# LDO.net
KiCad netlist of a schematic drawn in Altium Designer
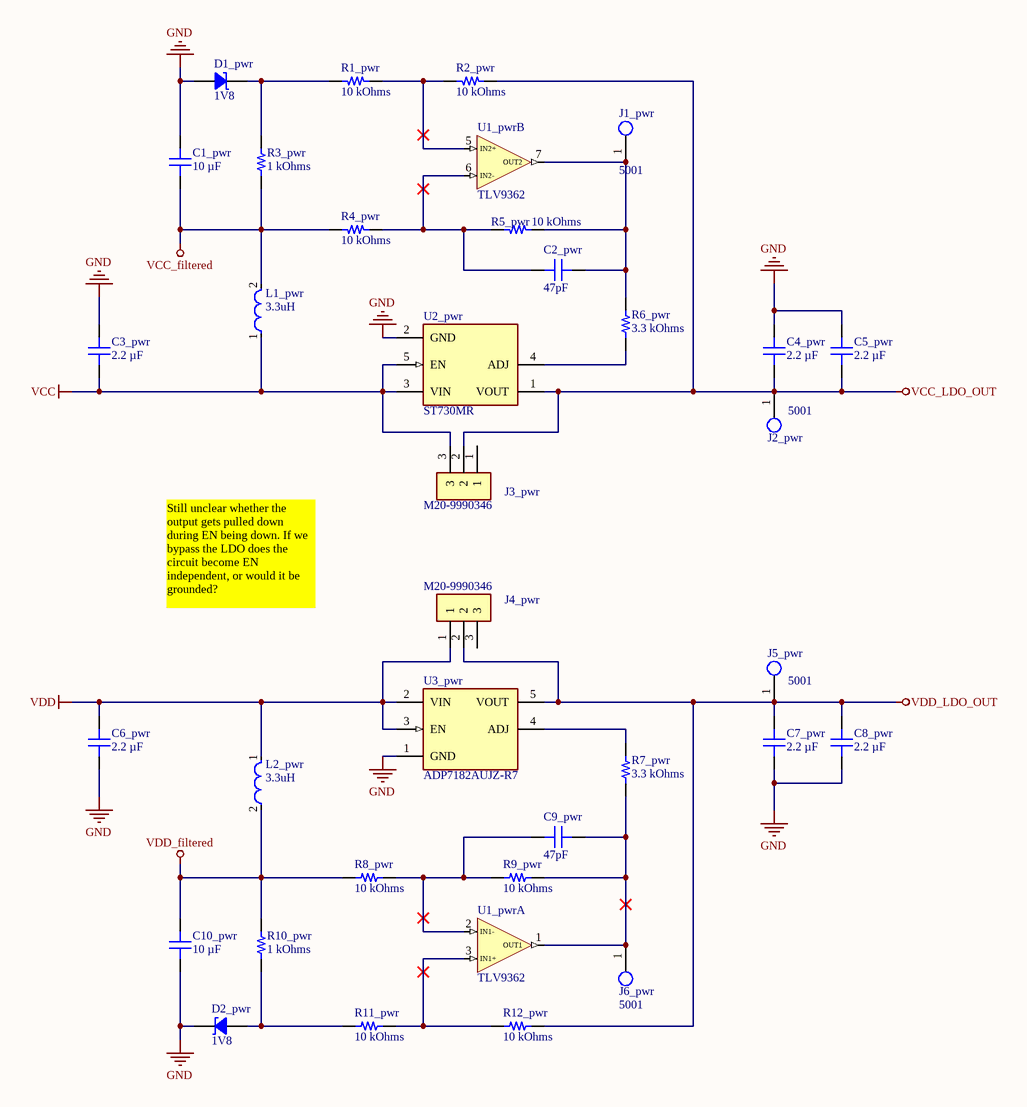
[diagram p0: LDO.SchDoc]

(export (version "E")
  (design (tool "Eeschema 10.0.6"))
  (components
    (comp (ref "C1_pwr")
      (value "10 µF")
      (footprint "CAP 1206_3216 - 0.8MM")
      (description "CAP CER 10UF 25V X7R 1206")
      (fields
        (field (name "PART NUMBER") "885012208069")
        (field (name "CAPACITANCE") "10 µF")
        (field (name "MANUFACTURER") "Würth Elektronik")
      )
      (libsource (lib "Celestial Altium Library - altium_library") (part "Capacitor"))
    )
    (comp (ref "C2_pwr")
      (value "47pF")
      (footprint "CAP 1206_3216 - 1.8MM")
      (description "CAP CER 47PF 1KV C0G/NP0 1206")
      (fields
        (field (name "PART NUMBER") "1206AA470KAT1A")
        (field (name "CAPACITANCE") "47pF")
        (field (name "MANUFACTURER") "AVX Corporation")
      )
      (libsource (lib "Celestial Altium Library - altium_library") (part "Capacitor"))
    )
    (comp (ref "C3_pwr")
      (value "2.2 µF")
      (footprint "CAP 1206_3216 - 0.8MM")
      (description "CAP CER 2.2UF 25V X7R 1206")
      (fields
        (field (name "PART NUMBER") "885382208001")
        (field (name "CAPACITANCE") "2.2 µF")
        (field (name "MANUFACTURER") "Würth Elektronik")
      )
      (libsource (lib "Celestial Altium Library - altium_library") (part "Capacitor"))
    )
    (comp (ref "C4_pwr")
      (value "2.2 µF")
      (footprint "CAP 1206_3216 - 0.8MM")
      (description "CAP CER 2.2UF 25V X7R 1206")
      (fields
        (field (name "PART NUMBER") "885382208001")
        (field (name "CAPACITANCE") "2.2 µF")
        (field (name "MANUFACTURER") "Würth Elektronik")
      )
      (libsource (lib "Celestial Altium Library - altium_library") (part "Capacitor"))
    )
    (comp (ref "C5_pwr")
      (value "2.2 µF")
      (footprint "CAP 1206_3216 - 0.8MM")
      (description "CAP CER 2.2UF 25V X7R 1206")
      (fields
        (field (name "PART NUMBER") "885382208001")
        (field (name "CAPACITANCE") "2.2 µF")
        (field (name "MANUFACTURER") "Würth Elektronik")
      )
      (libsource (lib "Celestial Altium Library - altium_library") (part "Capacitor"))
    )
    (comp (ref "C6_pwr")
      (value "2.2 µF")
      (footprint "CAP 1206_3216 - 0.8MM")
      (description "CAP CER 2.2UF 25V X7R 1206")
      (fields
        (field (name "PART NUMBER") "885382208001")
        (field (name "CAPACITANCE") "2.2 µF")
        (field (name "MANUFACTURER") "Würth Elektronik")
      )
      (libsource (lib "Celestial Altium Library - altium_library") (part "Capacitor"))
    )
    (comp (ref "C7_pwr")
      (value "2.2 µF")
      (footprint "CAP 1206_3216 - 0.8MM")
      (description "CAP CER 2.2UF 25V X7R 1206")
      (fields
        (field (name "PART NUMBER") "885382208001")
        (field (name "CAPACITANCE") "2.2 µF")
        (field (name "MANUFACTURER") "Würth Elektronik")
      )
      (libsource (lib "Celestial Altium Library - altium_library") (part "Capacitor"))
    )
    (comp (ref "C8_pwr")
      (value "2.2 µF")
      (footprint "CAP 1206_3216 - 0.8MM")
      (description "CAP CER 2.2UF 25V X7R 1206")
      (fields
        (field (name "PART NUMBER") "885382208001")
        (field (name "CAPACITANCE") "2.2 µF")
        (field (name "MANUFACTURER") "Würth Elektronik")
      )
      (libsource (lib "Celestial Altium Library - altium_library") (part "Capacitor"))
    )
    (comp (ref "C9_pwr")
      (value "47pF")
      (footprint "CAP 1206_3216 - 1.8MM")
      (description "CAP CER 47PF 1KV C0G/NP0 1206")
      (fields
        (field (name "PART NUMBER") "1206AA470KAT1A")
        (field (name "CAPACITANCE") "47pF")
        (field (name "MANUFACTURER") "AVX Corporation")
      )
      (libsource (lib "Celestial Altium Library - altium_library") (part "Capacitor"))
    )
    (comp (ref "C10_pwr")
      (value "10 µF")
      (footprint "CAP 1206_3216 - 0.8MM")
      (description "CAP CER 10UF 25V X7R 1206")
      (fields
        (field (name "PART NUMBER") "885012208069")
        (field (name "CAPACITANCE") "10 µF")
        (field (name "MANUFACTURER") "Würth Elektronik")
      )
      (libsource (lib "Celestial Altium Library - altium_library") (part "Capacitor"))
    )
    (comp (ref "D1_pwr")
      (value "1V8")
      (footprint "SOD323")
      (libsource (lib "za_koncar") (part "BZX38450-C1V8X"))
    )
    (comp (ref "D2_pwr")
      (value "1V8")
      (footprint "SOD323")
      (libsource (lib "za_koncar") (part "BZX38450-C1V8X"))
    )
    (comp (ref "J1_pwr")
      (value "5001")
      (footprint "FP-5001-MFG")
      (description "PC TEST POINT MINIATURE BLACK")
      (libsource (lib "za_koncar") (part "CMP-2000-05181-2"))
    )
    (comp (ref "J2_pwr")
      (value "5001")
      (footprint "FP-5001-MFG")
      (description "PC TEST POINT MINIATURE BLACK")
      (libsource (lib "za_koncar") (part "CMP-2000-05181-2"))
    )
    (comp (ref "J3_pwr")
      (value "M20-9990346")
      (footprint "HDRV3W64P0X254_1X3_762X254X864P - duplicate")
      (description "Connector")
      (fields (field (name "MOUSER PART NUMBER") "855-M20-9990346"))
      (libsource (lib "") (part "M20-9990346_1"))
    )
    (comp (ref "J4_pwr")
      (value "M20-9990346")
      (footprint "HDRV3W64P0X254_1X3_762X254X864P - duplicate")
      (description "Connector")
      (fields (field (name "MOUSER PART NUMBER") "855-M20-9990346"))
      (libsource (lib "za_koncar") (part "M20-9990346"))
    )
    (comp (ref "J5_pwr")
      (value "5001")
      (footprint "FP-5001-MFG")
      (description "PC TEST POINT MINIATURE BLACK")
      (libsource (lib "za_koncar") (part "CMP-2000-05181-2"))
    )
    (comp (ref "J6_pwr")
      (value "5001")
      (footprint "FP-5001-MFG")
      (description "PC TEST POINT MINIATURE BLACK")
      (libsource (lib "za_koncar") (part "CMP-2000-05181-2"))
    )
    (comp (ref "L1_pwr")
      (value "3.3uH")
      (footprint "FP-MLZ2012-1_25-IPC_B")
      (description "Shielded Multilayer Inductor 3.3uH ±20% 500mA 260mΩ SMD 0805")
      (fields (field (name "TOLERANCE") "20%"))
      (libsource (lib "") (part "MLZ2012M_1"))
    )
    (comp (ref "L2_pwr")
      (value "3.3uH")
      (footprint "FP-MLZ2012-1_25-IPC_B")
      (description "Shielded Multilayer Inductor 3.3uH ±20% 500mA 260mΩ SMD 0805")
      (fields (field (name "TOLERANCE") "20%"))
      (libsource (lib "za_koncar") (part "MLZ2012M"))
    )
    (comp (ref "R1_pwr")
      (value "10 kOhms")
      (footprint "YAGEO RES 1206_3216")
      (description "RES SMD 10K OHM 1% 1/4W 1206")
      (fields (field (name "PART NUMBER") "RT1206FRE0710KL") (field (name "MANUFACTURER") "Yageo"))
      (libsource (lib "Celestial Altium Library - altium_library") (part "Resistor"))
    )
    (comp (ref "R2_pwr")
      (value "10 kOhms")
      (footprint "YAGEO RES 1206_3216")
      (description "RES SMD 10K OHM 1% 1/4W 1206")
      (fields (field (name "PART NUMBER") "RT1206FRE0710KL") (field (name "MANUFACTURER") "Yageo"))
      (libsource (lib "Celestial Altium Library - altium_library") (part "Resistor"))
    )
    (comp (ref "R3_pwr")
      (value "1 kOhms")
      (footprint "YAGEO RES 1206_3216")
      (description "RES SMD 1K OHM 1% 1/4W 1206")
      (fields (field (name "PART NUMBER") "RT1206FRE071KL") (field (name "MANUFACTURER") "Yageo"))
      (libsource (lib "Celestial Altium Library - altium_library") (part "Resistor"))
    )
    (comp (ref "R4_pwr")
      (value "10 kOhms")
      (footprint "YAGEO RES 1206_3216")
      (description "RES SMD 10K OHM 1% 1/4W 1206")
      (fields (field (name "PART NUMBER") "RT1206FRE0710KL") (field (name "MANUFACTURER") "Yageo"))
      (libsource (lib "Celestial Altium Library - altium_library") (part "Resistor"))
    )
    (comp (ref "R5_pwr")
      (value "10 kOhms")
      (footprint "YAGEO RES 1206_3216")
      (description "RES SMD 10K OHM 1% 1/4W 1206")
      (fields (field (name "PART NUMBER") "RT1206FRE0710KL") (field (name "MANUFACTURER") "Yageo"))
      (libsource (lib "Celestial Altium Library - altium_library") (part "Resistor"))
    )
    (comp (ref "R6_pwr")
      (value "3.3 kOhms")
      (footprint "YAGEO RES 1206_3216")
      (description "RES SMD 3.3K OHM 1% 1/4W 1206")
      (fields (field (name "PART NUMBER") "RT1206FRE073K3L") (field (name "MANUFACTURER") "Yageo"))
      (libsource (lib "Celestial Altium Library - altium_library") (part "Resistor"))
    )
    (comp (ref "R7_pwr")
      (value "3.3 kOhms")
      (footprint "YAGEO RES 1206_3216")
      (description "RES SMD 3.3K OHM 1% 1/4W 1206")
      (fields (field (name "PART NUMBER") "RT1206FRE073K3L") (field (name "MANUFACTURER") "Yageo"))
      (libsource (lib "Celestial Altium Library - altium_library") (part "Resistor"))
    )
    (comp (ref "R8_pwr")
      (value "10 kOhms")
      (footprint "YAGEO RES 1206_3216")
      (description "RES SMD 10K OHM 1% 1/4W 1206")
      (fields (field (name "PART NUMBER") "RT1206FRE0710KL") (field (name "MANUFACTURER") "Yageo"))
      (libsource (lib "Celestial Altium Library - altium_library") (part "Resistor"))
    )
    (comp (ref "R9_pwr")
      (value "10 kOhms")
      (footprint "YAGEO RES 1206_3216")
      (description "RES SMD 10K OHM 1% 1/4W 1206")
      (fields (field (name "PART NUMBER") "RT1206FRE0710KL") (field (name "MANUFACTURER") "Yageo"))
      (libsource (lib "Celestial Altium Library - altium_library") (part "Resistor"))
    )
    (comp (ref "R10_pwr")
      (value "1 kOhms")
      (footprint "YAGEO RES 1206_3216")
      (description "RES SMD 1K OHM 1% 1/4W 1206")
      (fields (field (name "PART NUMBER") "RT1206FRE071KL") (field (name "MANUFACTURER") "Yageo"))
      (libsource (lib "Celestial Altium Library - altium_library") (part "Resistor"))
    )
    (comp (ref "R11_pwr")
      (value "10 kOhms")
      (footprint "YAGEO RES 1206_3216")
      (description "RES SMD 10K OHM 1% 1/4W 1206")
      (fields (field (name "PART NUMBER") "RT1206FRE0710KL") (field (name "MANUFACTURER") "Yageo"))
      (libsource (lib "Celestial Altium Library - altium_library") (part "Resistor"))
    )
    (comp (ref "R12_pwr")
      (value "10 kOhms")
      (footprint "YAGEO RES 1206_3216")
      (description "RES SMD 10K OHM 1% 1/4W 1206")
      (fields (field (name "PART NUMBER") "RT1206FRE0710KL") (field (name "MANUFACTURER") "Yageo"))
      (libsource (lib "Celestial Altium Library - altium_library") (part "Resistor"))
    )
    (comp (ref "U1_pwr")
      (value "TLV9362")
      (footprint "za_koncar:SOIC8-127P600X175-8N")
      (description "TLV936x 10-MHz, 40-V, RRO, Operational Amplifie")
      (libsource (lib "za_koncar") (part "TLV9362"))
    )
    (comp (ref "U2_pwr")
      (value "ST730MR")
      (footprint "FP-UJ-5-IPC_B")
      (libsource (lib "za_koncar") (part "ST730MR"))
    )
    (comp (ref "U3_pwr")
      (value "ADP7182AUJZ-R7")
      (footprint "FP-UJ-5-IPC_B")
      (description "IC REG LIN NEG ADJ 200MA 5TSOT")
      (fields
        (field (name "MANUFACTURER") "Analog Devices")
        (field (name "OCTOPART") "https://octopart.com/adp7182aujz-r7-analog+devices-21054665")
      )
      (libsource (lib "za_koncar") (part "ADP7182"))
    )
  )
  (nets
    (net (code "1") (name "GND") (class "Default")
      (node (ref "C10_pwr") (pin "1") (pinfunction "1_1") (pintype "passive"))
      (node (ref "C1_pwr") (pin "1") (pinfunction "1_1") (pintype "passive"))
      (node (ref "C3_pwr") (pin "1") (pinfunction "1_1") (pintype "passive"))
      (node (ref "C4_pwr") (pin "1") (pinfunction "1_1") (pintype "passive"))
      (node (ref "C5_pwr") (pin "1") (pinfunction "1_1") (pintype "passive"))
      (node (ref "C6_pwr") (pin "1") (pinfunction "1_1") (pintype "passive"))
      (node (ref "C7_pwr") (pin "1") (pinfunction "1_1") (pintype "passive"))
      (node (ref "C8_pwr") (pin "1") (pinfunction "1_1") (pintype "passive"))
      (node (ref "D1_pwr") (pin "1") (pinfunction "1_1") (pintype "passive"))
      (node (ref "D2_pwr") (pin "2") (pinfunction "2_2") (pintype "passive"))
      (node (ref "U2_pwr") (pin "2") (pinfunction "GND_2") (pintype "power_in"))
      (node (ref "U3_pwr") (pin "1") (pinfunction "GND_1") (pintype "power_in"))
    )
    (net (code "2") (name "Net-(D1_pwr-Pad2)") (class "Default")
      (node (ref "D1_pwr") (pin "2") (pinfunction "2_2") (pintype "passive"))
      (node (ref "R1_pwr") (pin "2") (pinfunction "2_2") (pintype "passive"))
      (node (ref "R3_pwr") (pin "2") (pinfunction "2_2") (pintype "passive"))
    )
    (net (code "3") (name "Net-(D2_pwr-Pad1)") (class "Default")
      (node (ref "D2_pwr") (pin "1") (pinfunction "1_1") (pintype "passive"))
      (node (ref "R10_pwr") (pin "1") (pinfunction "1_1") (pintype "passive"))
      (node (ref "R11_pwr") (pin "2") (pinfunction "2_2") (pintype "passive"))
    )
    (net (code "4") (name "Net-(U1_pwrA-IN1+)") (class "Default")
      (node (ref "R11_pwr") (pin "1") (pinfunction "1_1") (pintype "passive"))
      (node (ref "R12_pwr") (pin "2") (pinfunction "2_2") (pintype "passive"))
      (node (ref "U1_pwr") (pin "3") (pinfunction "IN1+_3") (pintype "input"))
    )
    (net (code "5") (name "Net-(U1_pwrA-IN1-)") (class "Default")
      (node (ref "C9_pwr") (pin "1") (pinfunction "1_1") (pintype "passive"))
      (node (ref "R8_pwr") (pin "1") (pinfunction "1_1") (pintype "passive"))
      (node (ref "R9_pwr") (pin "2") (pinfunction "2_2") (pintype "passive"))
      (node (ref "U1_pwr") (pin "2") (pinfunction "IN1-_2") (pintype "input"))
    )
    (net (code "6") (name "Net-(U1_pwrA-OUT1)") (class "Default")
      (node (ref "C9_pwr") (pin "2") (pinfunction "2_2") (pintype "passive"))
      (node (ref "J6_pwr") (pin "1") (pinfunction "1_1") (pintype "passive"))
      (node (ref "R7_pwr") (pin "2") (pinfunction "2_2") (pintype "passive"))
      (node (ref "R9_pwr") (pin "1") (pinfunction "1_1") (pintype "passive"))
      (node (ref "U1_pwr") (pin "1") (pinfunction "OUT1_1") (pintype "output"))
    )
    (net (code "7") (name "Net-(U1_pwrB-IN2+)") (class "Default")
      (node (ref "R1_pwr") (pin "1") (pinfunction "1_1") (pintype "passive"))
      (node (ref "R2_pwr") (pin "2") (pinfunction "2_2") (pintype "passive"))
      (node (ref "U1_pwr") (pin "5") (pinfunction "IN2+_5") (pintype "input"))
    )
    (net (code "8") (name "Net-(U1_pwrB-IN2-)") (class "Default")
      (node (ref "C2_pwr") (pin "1") (pinfunction "1_1") (pintype "passive"))
      (node (ref "R4_pwr") (pin "1") (pinfunction "1_1") (pintype "passive"))
      (node (ref "R5_pwr") (pin "2") (pinfunction "2_2") (pintype "passive"))
      (node (ref "U1_pwr") (pin "6") (pinfunction "IN2-_6") (pintype "input"))
    )
    (net (code "9") (name "Net-(U1_pwrB-OUT2)") (class "Default")
      (node (ref "C2_pwr") (pin "2") (pinfunction "2_2") (pintype "passive"))
      (node (ref "J1_pwr") (pin "1") (pinfunction "1_1") (pintype "passive"))
      (node (ref "R5_pwr") (pin "1") (pinfunction "1_1") (pintype "passive"))
      (node (ref "R6_pwr") (pin "1") (pinfunction "1_1") (pintype "passive"))
      (node (ref "U1_pwr") (pin "7") (pinfunction "OUT2_7") (pintype "output"))
    )
    (net (code "10") (name "Net-(U2_pwr-ADJ)") (class "Default")
      (node (ref "R6_pwr") (pin "2") (pinfunction "2_2") (pintype "passive"))
      (node (ref "U2_pwr") (pin "4") (pinfunction "ADJ_4") (pintype "passive"))
    )
    (net (code "11") (name "Net-(U3_pwr-ADJ)") (class "Default")
      (node (ref "R7_pwr") (pin "1") (pinfunction "1_1") (pintype "passive"))
      (node (ref "U3_pwr") (pin "4") (pinfunction "ADJ_4") (pintype "passive"))
    )
    (net (code "12") (name "VCC") (class "Default")
      (node (ref "C3_pwr") (pin "2") (pinfunction "2_2") (pintype "passive"))
      (node (ref "J3_pwr") (pin "3") (pinfunction "3_3") (pintype "passive"))
      (node (ref "L1_pwr") (pin "1") (pinfunction "1_1") (pintype "passive"))
      (node (ref "U2_pwr") (pin "3") (pinfunction "VIN_3") (pintype "power_in"))
      (node (ref "U2_pwr") (pin "5") (pinfunction "EN_5") (pintype "input"))
    )
    (net (code "13") (name "VCC_LDO_OUT") (class "Default")
      (node (ref "C4_pwr") (pin "2") (pinfunction "2_2") (pintype "passive"))
      (node (ref "C5_pwr") (pin "2") (pinfunction "2_2") (pintype "passive"))
      (node (ref "J2_pwr") (pin "1") (pinfunction "1_1") (pintype "passive"))
      (node (ref "J3_pwr") (pin "2") (pinfunction "2_2") (pintype "passive"))
      (node (ref "R2_pwr") (pin "1") (pinfunction "1_1") (pintype "passive"))
      (node (ref "U2_pwr") (pin "1") (pinfunction "VOUT_1") (pintype "power_in"))
    )
    (net (code "14") (name "VCC_filtered") (class "Default")
      (node (ref "C1_pwr") (pin "2") (pinfunction "2_2") (pintype "passive"))
      (node (ref "L1_pwr") (pin "2") (pinfunction "2_2") (pintype "passive"))
      (node (ref "R3_pwr") (pin "1") (pinfunction "1_1") (pintype "passive"))
      (node (ref "R4_pwr") (pin "2") (pinfunction "2_2") (pintype "passive"))
    )
    (net (code "15") (name "VDD") (class "Default")
      (node (ref "C6_pwr") (pin "2") (pinfunction "2_2") (pintype "passive"))
      (node (ref "J4_pwr") (pin "1") (pinfunction "1_1") (pintype "passive"))
      (node (ref "L2_pwr") (pin "1") (pinfunction "1_1") (pintype "passive"))
      (node (ref "U3_pwr") (pin "2") (pinfunction "VIN_2") (pintype "power_in"))
      (node (ref "U3_pwr") (pin "3") (pinfunction "EN_3") (pintype "input"))
    )
    (net (code "16") (name "VDD_LDO_OUT") (class "Default")
      (node (ref "C7_pwr") (pin "2") (pinfunction "2_2") (pintype "passive"))
      (node (ref "C8_pwr") (pin "2") (pinfunction "2_2") (pintype "passive"))
      (node (ref "J4_pwr") (pin "2") (pinfunction "2_2") (pintype "passive"))
      (node (ref "J5_pwr") (pin "1") (pinfunction "1_1") (pintype "passive"))
      (node (ref "R12_pwr") (pin "1") (pinfunction "1_1") (pintype "passive"))
      (node (ref "U3_pwr") (pin "5") (pinfunction "VOUT_5") (pintype "power_in"))
    )
    (net (code "17") (name "VDD_filtered") (class "Default")
      (node (ref "C10_pwr") (pin "2") (pinfunction "2_2") (pintype "passive"))
      (node (ref "L2_pwr") (pin "2") (pinfunction "2_2") (pintype "passive"))
      (node (ref "R10_pwr") (pin "2") (pinfunction "2_2") (pintype "passive"))
      (node (ref "R8_pwr") (pin "2") (pinfunction "2_2") (pintype "passive"))
    )
    (net (code "18") (name "unconnected-(J3_pwr-Pad1)") (class "Default")
      (node (ref "J3_pwr") (pin "1") (pinfunction "1_1") (pintype "passive"))
    )
    (net (code "19") (name "unconnected-(J4_pwr-Pad3)") (class "Default")
      (node (ref "J4_pwr") (pin "3") (pinfunction "3_3") (pintype "passive"))
    )
  )
)
